# IP2366_DEMO_V1_41_1.net
KiCad netlist of a schematic drawn in Altium Designer
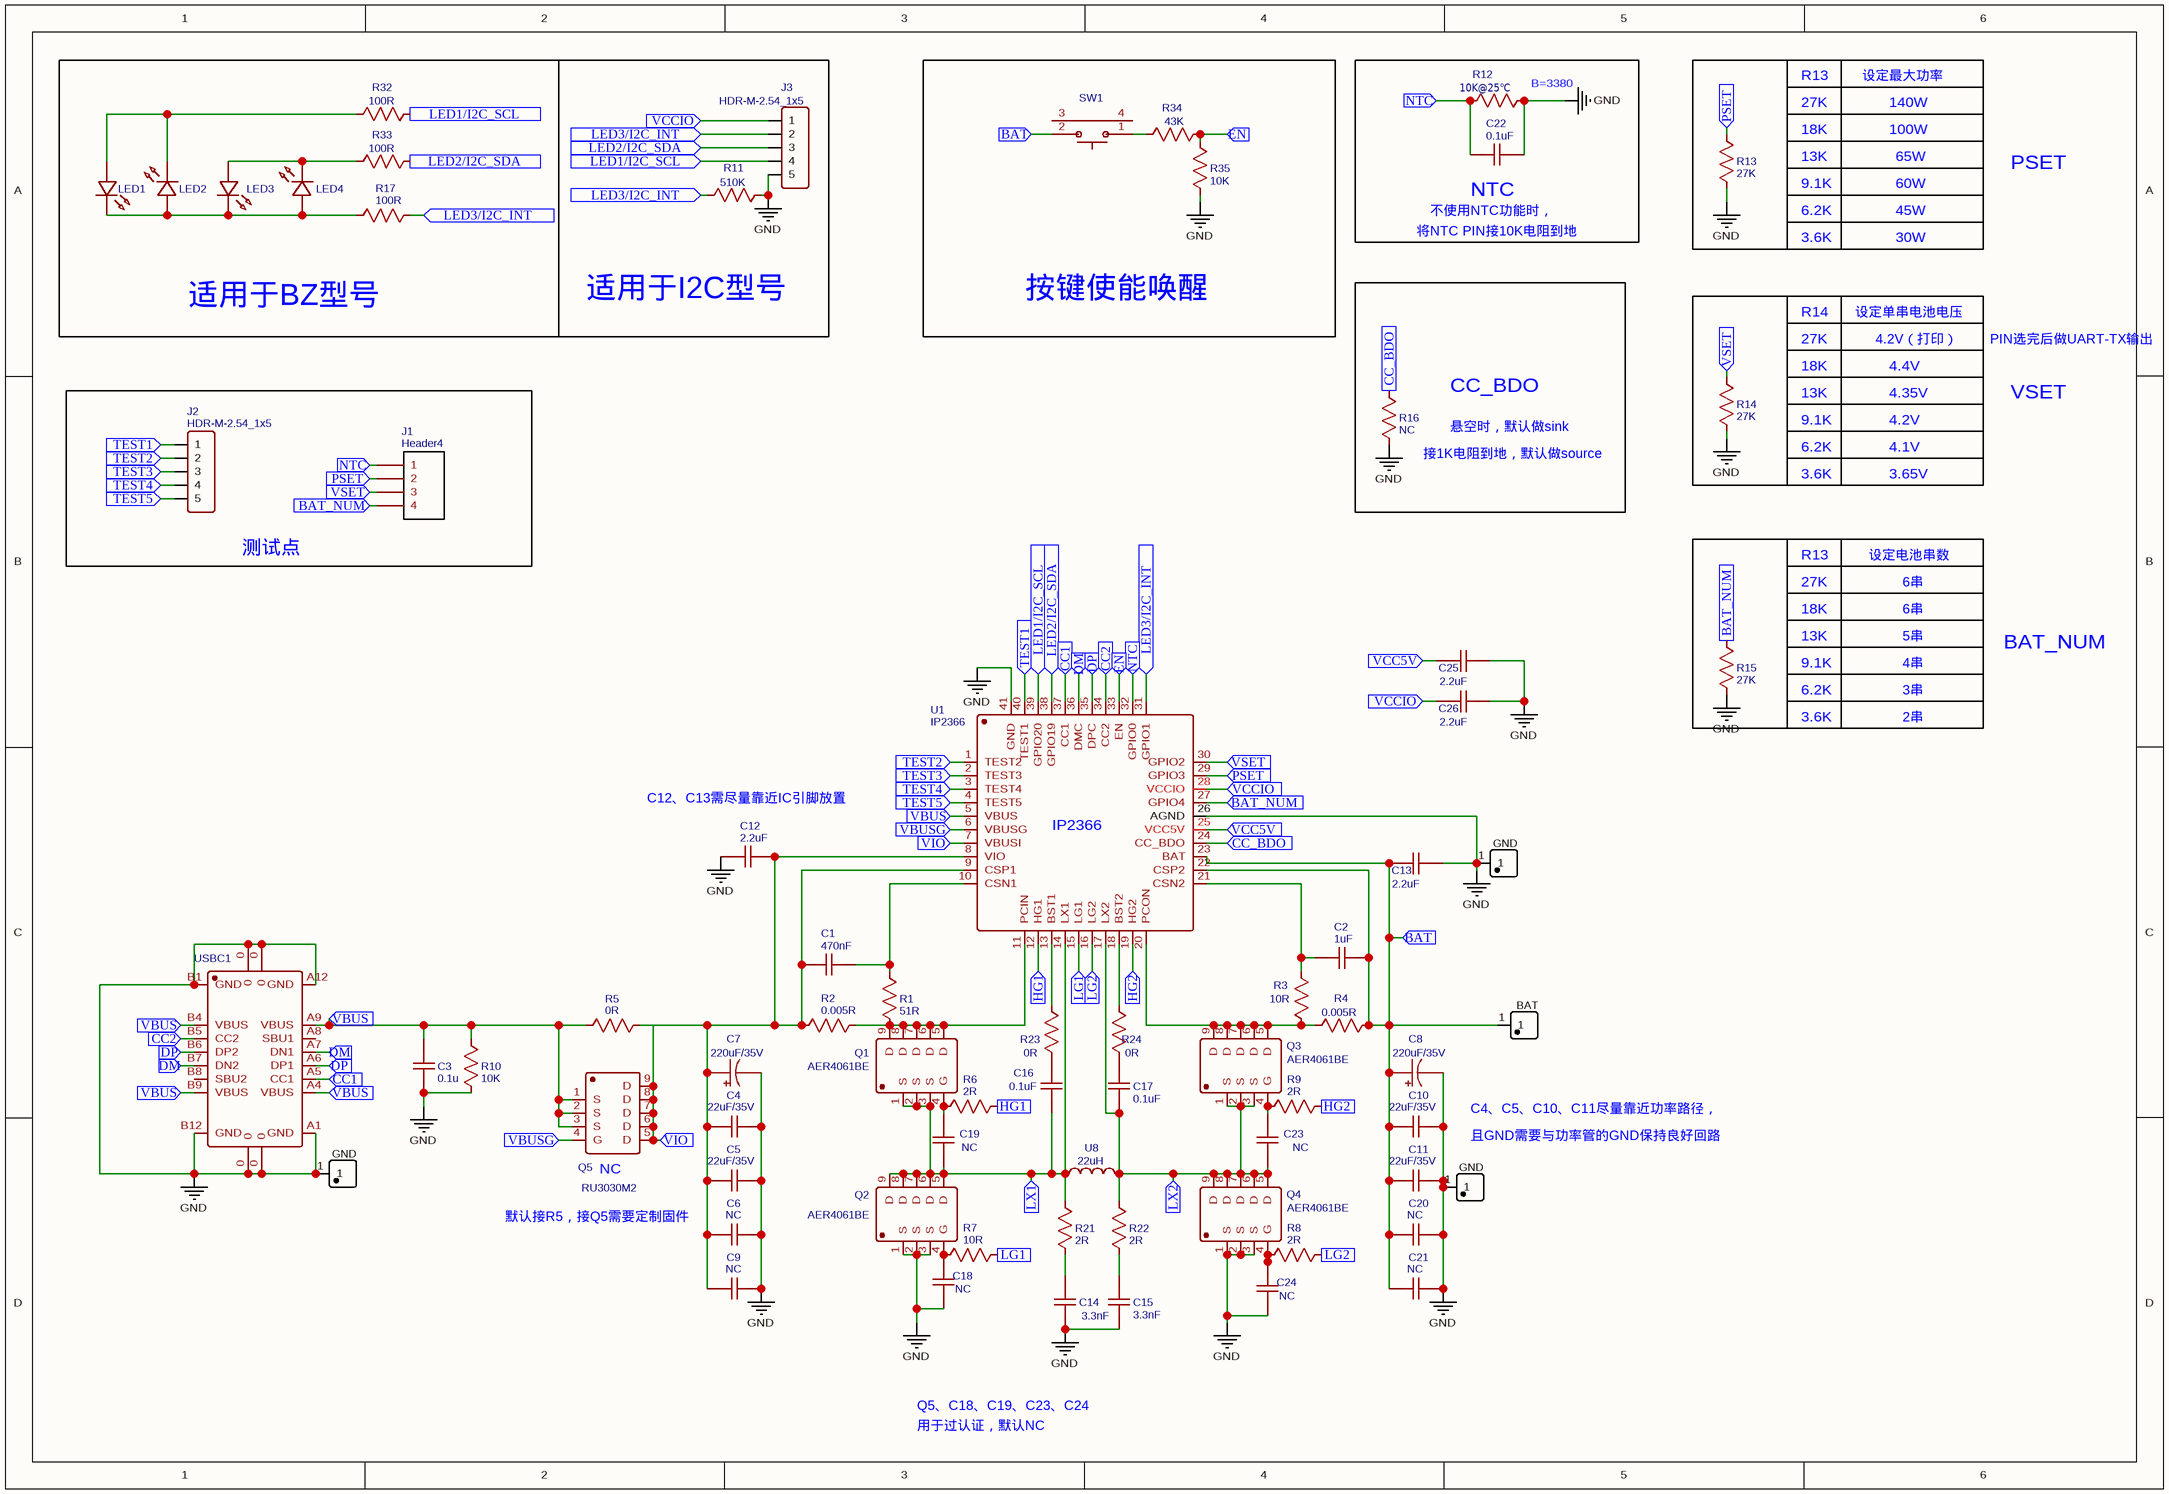
[diagram p0: IP2366_DEMO_V1.41(1).schdoc]

(export (version "E")
  (design (tool "Eeschema 10.0.6"))
  (components
    (comp (ref "C1")
      (value "470nF")
      (fields (field (name "CONTRIBUTOR") "LCEDA_Lib"))
      (libsource (lib "altium-import") (part "root_0_470nF_"))
    )
    (comp (ref "C2")
      (value "1uF")
      (fields (field (name "CONTRIBUTOR") "LCEDA_Lib"))
      (libsource (lib "altium-import") (part "root_0_1uF_"))
    )
    (comp (ref "C3")
      (value "0.1u")
      (fields (field (name "CONTRIBUTOR") "LCEDA_Lib"))
      (libsource (lib "altium-import") (part "root_1_0.1u_"))
    )
    (comp (ref "C4")
      (value "22uF/35V")
      (fields (field (name "CONTRIBUTOR") "LCEDA_Lib"))
      (libsource (lib "altium-import") (part "root_0_22uF/35V_"))
    )
    (comp (ref "C5")
      (value "22uF/35V")
      (fields (field (name "CONTRIBUTOR") "LCEDA_Lib"))
      (libsource (lib "altium-import") (part "root_0_22uF/35V_"))
    )
    (comp (ref "C6")
      (value "NC")
      (fields (field (name "CONTRIBUTOR") "LCEDA_Lib"))
      (libsource (lib "altium-import") (part "root_0_NC_"))
    )
    (comp (ref "C7")
      (value "220uF/35V")
      (fields
        (field (name "BOM_SUPPLIER PART") "C365767")
        (field (name "BOM_MANUFACTURER PART") "RC050M4R7LO5*11TH-2A1E")
        (field (name "CONTRIBUTOR") "s-dawn")
      )
      (libsource (lib "altium-import") (part "root_1_220uF/35V_"))
    )
    (comp (ref "C8")
      (value "220uF/35V")
      (fields
        (field (name "BOM_SUPPLIER PART") "C365767")
        (field (name "BOM_MANUFACTURER PART") "RC050M4R7LO5*11TH-2A1E")
        (field (name "CONTRIBUTOR") "s-dawn")
      )
      (libsource (lib "altium-import") (part "root_1_220uF/35V_"))
    )
    (comp (ref "C9")
      (value "NC")
      (fields (field (name "CONTRIBUTOR") "LCEDA_Lib"))
      (libsource (lib "altium-import") (part "root_0_NC_"))
    )
    (comp (ref "C10")
      (value "22uF/35V")
      (fields (field (name "CONTRIBUTOR") "LCEDA_Lib"))
      (libsource (lib "altium-import") (part "root_0_22uF/35V_"))
    )
    (comp (ref "C11")
      (value "22uF/35V")
      (fields (field (name "CONTRIBUTOR") "LCEDA_Lib"))
      (libsource (lib "altium-import") (part "root_0_22uF/35V_"))
    )
    (comp (ref "C12")
      (value "2.2uF")
      (fields (field (name "CONTRIBUTOR") "LCEDA_Lib"))
      (libsource (lib "altium-import") (part "root_0_2.2uF_"))
    )
    (comp (ref "C13")
      (value "2.2uF")
      (fields (field (name "CONTRIBUTOR") "LCEDA_Lib"))
      (libsource (lib "altium-import") (part "root_0_2.2uF_"))
    )
    (comp (ref "C14")
      (value "3.3nF")
      (fields (field (name "CONTRIBUTOR") "LCEDA_Lib"))
      (libsource (lib "altium-import") (part "root_3_3.3nF_"))
    )
    (comp (ref "C15")
      (value "3.3nF")
      (fields (field (name "CONTRIBUTOR") "LCEDA_Lib"))
      (libsource (lib "altium-import") (part "root_3_3.3nF_"))
    )
    (comp (ref "C16")
      (value "0.1uF")
      (fields (field (name "CONTRIBUTOR") "LCEDA_Lib"))
      (libsource (lib "altium-import") (part "root_3_0.1uF_"))
    )
    (comp (ref "C17")
      (value "0.1uF")
      (fields (field (name "CONTRIBUTOR") "LCEDA_Lib"))
      (libsource (lib "altium-import") (part "root_3_0.1uF_"))
    )
    (comp (ref "C18")
      (value "NC")
      (fields (field (name "CONTRIBUTOR") "LCEDA_Lib"))
      (libsource (lib "altium-import") (part "root_3_NC_"))
    )
    (comp (ref "C19")
      (value "NC")
      (fields (field (name "CONTRIBUTOR") "LCEDA_Lib"))
      (libsource (lib "altium-import") (part "root_3_NC_"))
    )
    (comp (ref "C20")
      (value "NC")
      (fields (field (name "CONTRIBUTOR") "LCEDA_Lib"))
      (libsource (lib "altium-import") (part "root_0_NC_"))
    )
    (comp (ref "C21")
      (value "NC")
      (fields (field (name "CONTRIBUTOR") "LCEDA_Lib"))
      (libsource (lib "altium-import") (part "root_0_NC_"))
    )
    (comp (ref "C22")
      (value "0.1uF")
      (fields (field (name "CONTRIBUTOR") "LCEDA_Lib"))
      (libsource (lib "altium-import") (part "root_0_0.1uF_"))
    )
    (comp (ref "C23")
      (value "NC")
      (fields (field (name "CONTRIBUTOR") "LCEDA_Lib"))
      (libsource (lib "altium-import") (part "root_3_NC_"))
    )
    (comp (ref "C24")
      (value "NC")
      (fields (field (name "CONTRIBUTOR") "LCEDA_Lib"))
      (libsource (lib "altium-import") (part "root_3_NC_"))
    )
    (comp (ref "C25")
      (value "2.2uF")
      (fields (field (name "CONTRIBUTOR") "LCEDA_Lib"))
      (libsource (lib "altium-import") (part "root_0_2.2uF_"))
    )
    (comp (ref "C26")
      (value "2.2uF")
      (fields (field (name "CONTRIBUTOR") "LCEDA_Lib"))
      (libsource (lib "altium-import") (part "root_0_2.2uF_"))
    )
    (comp (ref "J1")
      (value "Header4")
      (fields (field (name "CONTRIBUTOR") "hrqmmm1"))
      (libsource (lib "altium-import") (part "root_2_Header4_"))
    )
    (comp (ref "J2")
      (value "HDR-M-2.54_1x5")
      (fields (field (name "BOM_SUPPLIER PART") "C358687") (field (name "CONTRIBUTOR") "LCEDA_Lib"))
      (libsource (lib "altium-import") (part "root_0_HDR-M-2.54_1x5_"))
    )
    (comp (ref "J3")
      (value "HDR-M-2.54_1x5")
      (fields (field (name "BOM_SUPPLIER PART") "C358687") (field (name "CONTRIBUTOR") "LCEDA_Lib"))
      (libsource (lib "altium-import") (part "root_0_HDR-M-2.54_1x5_"))
    )
    (comp (ref "LED1")
      (value "LED-0603_B")
      (fields
        (field (name "BOM_MANUFACTURER PART") "19-217/BHC-ZL1M2RY/3T")
        (field (name "BOM_SUPPLIER PART") "C72041")
        (field (name "CONTRIBUTOR") "LCEDA_01")
      )
      (libsource (lib "altium-import") (part "root_3_LED-0603_B_"))
    )
    (comp (ref "LED2")
      (value "LED-0603_B")
      (fields
        (field (name "BOM_MANUFACTURER PART") "19-217/BHC-ZL1M2RY/3T")
        (field (name "BOM_SUPPLIER PART") "C72041")
        (field (name "CONTRIBUTOR") "LCEDA_01")
      )
      (libsource (lib "altium-import") (part "root_1_LED-0603_B_"))
    )
    (comp (ref "LED3")
      (value "LED-0603_B")
      (fields
        (field (name "BOM_MANUFACTURER PART") "19-217/BHC-ZL1M2RY/3T")
        (field (name "BOM_SUPPLIER PART") "C72041")
        (field (name "CONTRIBUTOR") "LCEDA_01")
      )
      (libsource (lib "altium-import") (part "root_3_LED-0603_B_"))
    )
    (comp (ref "LED4")
      (value "LED-0603_B")
      (fields
        (field (name "BOM_MANUFACTURER PART") "19-217/BHC-ZL1M2RY/3T")
        (field (name "BOM_SUPPLIER PART") "C72041")
        (field (name "CONTRIBUTOR") "LCEDA_01")
      )
      (libsource (lib "altium-import") (part "root_1_LED-0603_B_"))
    )
    (comp (ref "Q1")
      (value "AER4061BE")
      (fields
        (field (name "BOM_MANUFACTURER PART") "RU3090M")
        (field (name "BOM_SUPPLIER PART") "C160654")
        (field (name "CONTRIBUTOR") "LCSC")
      )
      (libsource (lib "altium-import") (part "root_1_AER4061BE_"))
    )
    (comp (ref "Q2")
      (value "AER4061BE")
      (fields
        (field (name "BOM_MANUFACTURER PART") "RU3090M")
        (field (name "BOM_SUPPLIER PART") "C160654")
        (field (name "CONTRIBUTOR") "LCSC")
      )
      (libsource (lib "altium-import") (part "root_1_AER4061BE_"))
    )
    (comp (ref "Q3")
      (value "AER4061BE")
      (fields
        (field (name "BOM_MANUFACTURER PART") "RU3090M")
        (field (name "BOM_SUPPLIER PART") "C160654")
        (field (name "CONTRIBUTOR") "LCSC")
      )
      (libsource (lib "altium-import") (part "root_1_AER4061BE_"))
    )
    (comp (ref "Q4")
      (value "AER4061BE")
      (fields
        (field (name "BOM_MANUFACTURER PART") "RU3090M")
        (field (name "BOM_SUPPLIER PART") "C160654")
        (field (name "CONTRIBUTOR") "LCSC")
      )
      (libsource (lib "altium-import") (part "root_1_AER4061BE_"))
    )
    (comp (ref "Q5")
      (value "RU3030M2")
      (fields (field (name "BOM_SUPPLIER PART") "C180957") (field (name "CONTRIBUTOR") "LCSC"))
      (libsource (lib "altium-import") (part "root_0_RU3030M2_"))
    )
    (comp (ref "R1")
      (value "51R")
      (fields (field (name "CONTRIBUTOR") "LCEDA_Lib"))
      (libsource (lib "altium-import") (part "root_1_51R_"))
    )
    (comp (ref "R2")
      (value "0.005R")
      (fields (field (name "CONTRIBUTOR") "LCEDA_Lib"))
      (libsource (lib "altium-import") (part "root_0_0.005R_"))
    )
    (comp (ref "R3")
      (value "10R")
      (fields (field (name "CONTRIBUTOR") "LCEDA_Lib"))
      (libsource (lib "altium-import") (part "root_1_10R_"))
    )
    (comp (ref "R4")
      (value "0.005R")
      (fields (field (name "CONTRIBUTOR") "LCEDA_Lib"))
      (libsource (lib "altium-import") (part "root_0_0.005R_"))
    )
    (comp (ref "R5")
      (value "0R")
      (fields (field (name "CONTRIBUTOR") "LCEDA_Lib"))
      (libsource (lib "altium-import") (part "root_0_0R_"))
    )
    (comp (ref "R6")
      (value "2R")
      (fields (field (name "CONTRIBUTOR") "LCEDA_Lib"))
      (libsource (lib "altium-import") (part "root_0_2R_"))
    )
    (comp (ref "R7")
      (value "10R")
      (fields (field (name "CONTRIBUTOR") "LCEDA_Lib"))
      (libsource (lib "altium-import") (part "root_0_10R_"))
    )
    (comp (ref "R8")
      (value "2R")
      (fields (field (name "CONTRIBUTOR") "LCEDA_Lib"))
      (libsource (lib "altium-import") (part "root_0_2R_"))
    )
    (comp (ref "R9")
      (value "2R")
      (fields (field (name "CONTRIBUTOR") "LCEDA_Lib"))
      (libsource (lib "altium-import") (part "root_0_2R_"))
    )
    (comp (ref "R10")
      (value "10K")
      (fields (field (name "CONTRIBUTOR") "LCEDA_Lib"))
      (libsource (lib "altium-import") (part "root_3_10K_"))
    )
    (comp (ref "R11")
      (value "510K")
      (fields (field (name "CONTRIBUTOR") "LCEDA_Lib"))
      (libsource (lib "altium-import") (part "root_0_510K_"))
    )
    (comp (ref "R12")
      (value "10K@25℃")
      (fields (field (name "CONTRIBUTOR") "LCEDA_Lib"))
      (libsource (lib "altium-import") (part "root_2_10K@25℃_"))
    )
    (comp (ref "R13")
      (value "27K")
      (fields (field (name "CONTRIBUTOR") "LCEDA_Lib"))
      (libsource (lib "altium-import") (part "root_1_27K_"))
    )
    (comp (ref "R14")
      (value "27K")
      (fields (field (name "CONTRIBUTOR") "LCEDA_Lib"))
      (libsource (lib "altium-import") (part "root_1_27K_"))
    )
    (comp (ref "R15")
      (value "27K")
      (fields (field (name "CONTRIBUTOR") "LCEDA_Lib"))
      (libsource (lib "altium-import") (part "root_1_27K_"))
    )
    (comp (ref "R16")
      (value "NC")
      (fields (field (name "CONTRIBUTOR") "LCEDA_Lib"))
      (libsource (lib "altium-import") (part "root_1_NC_"))
    )
    (comp (ref "R17")
      (value "100R")
      (fields (field (name "CONTRIBUTOR") "LCEDA_Lib"))
      (libsource (lib "altium-import") (part "root_0_100R_"))
    )
    (comp (ref "R21")
      (value "2R")
      (fields (field (name "CONTRIBUTOR") "LCEDA_Lib"))
      (libsource (lib "altium-import") (part "root_1_2R_"))
    )
    (comp (ref "R22")
      (value "2R")
      (fields (field (name "CONTRIBUTOR") "LCEDA_Lib"))
      (libsource (lib "altium-import") (part "root_1_2R_"))
    )
    (comp (ref "R23")
      (value "0R")
      (fields (field (name "CONTRIBUTOR") "LCEDA_Lib"))
      (libsource (lib "altium-import") (part "root_3_0R_"))
    )
    (comp (ref "R24")
      (value "0R")
      (fields (field (name "CONTRIBUTOR") "LCEDA_Lib"))
      (libsource (lib "altium-import") (part "root_1_0R_"))
    )
    (comp (ref "R32")
      (value "100R")
      (fields (field (name "CONTRIBUTOR") "LCEDA_Lib"))
      (libsource (lib "altium-import") (part "root_2_100R_"))
    )
    (comp (ref "R33")
      (value "100R")
      (fields (field (name "CONTRIBUTOR") "LCEDA_Lib"))
      (libsource (lib "altium-import") (part "root_2_100R_"))
    )
    (comp (ref "R34")
      (value "43K")
      (fields (field (name "CONTRIBUTOR") "LCEDA_Lib"))
      (libsource (lib "altium-import") (part "root_2_43K_"))
    )
    (comp (ref "R35")
      (value "10K")
      (fields (field (name "CONTRIBUTOR") "LCEDA_Lib"))
      (libsource (lib "altium-import") (part "root_3_10K_"))
    )
    (comp (ref "SW1")
      (value "1TS002G-1900-3500-CT")
      (fields (field (name "BOM_SUPPLIER PART") "C319376") (field (name "CONTRIBUTOR") "LCSC"))
      (libsource (lib "altium-import") (part "root_2_1TS002G-1900-3500-CT_"))
    )
    (comp (ref "U1")
      (value "IP2366")
      (fields (field (name "CONTRIBUTOR") "cong24"))
      (libsource (lib "altium-import") (part "root_0_IP2366_"))
    )
    (comp (ref "U3")
      (value "GND")
      (fields
        (field (name "BOM_SUPPLIER PART") "C9900007423")
        (field (name "BOM_MANUFACTURER PART") "TP-红色测试点")
        (field (name "CONTRIBUTOR") "lcsc")
      )
      (libsource (lib "altium-import") (part "root_2_GND_"))
    )
    (comp (ref "U4")
      (value "BAT")
      (fields
        (field (name "BOM_SUPPLIER PART") "C9900007423")
        (field (name "BOM_MANUFACTURER PART") "TP-红色测试点")
        (field (name "CONTRIBUTOR") "lcsc")
      )
      (libsource (lib "altium-import") (part "root_2_BAT_"))
    )
    (comp (ref "U5")
      (value "GND")
      (fields
        (field (name "BOM_SUPPLIER PART") "C9900007423")
        (field (name "BOM_MANUFACTURER PART") "TP-红色测试点")
        (field (name "CONTRIBUTOR") "lcsc")
      )
      (libsource (lib "altium-import") (part "root_2_GND_"))
    )
    (comp (ref "U8")
      (value "22uH")
      (fields
        (field (name "BOM_SUPPLIER PART") "C3011538")
        (field (name "BOM_MANUFACTURER PART") "PDMTAT068125-100MLU")
        (field (name "CONTRIBUTOR") "lcsc")
      )
      (libsource (lib "altium-import") (part "root_0_22uH_"))
    )
    (comp (ref "U9")
      (value "GND")
      (fields
        (field (name "BOM_SUPPLIER PART") "C9900007423")
        (field (name "BOM_MANUFACTURER PART") "TP-红色测试点")
        (field (name "CONTRIBUTOR") "lcsc")
      )
      (libsource (lib "altium-import") (part "root_2_GND_"))
    )
    (comp (ref "USBC1")
      (value "TYPE-C-31-M-12")
      (fields (field (name "BOM_SUPPLIER PART") "C165948") (field (name "CONTRIBUTOR") "LCSC"))
      (libsource (lib "altium-import") (part "root_0_TYPE-C-31-M-12_"))
    )
  )
  (nets
    (net (code "1") (name "/BAT") (class "Default")
      (node (ref "C10") (pin "1") (pinfunction "1_1") (pintype "passive"))
      (node (ref "C11") (pin "1") (pinfunction "1_1") (pintype "passive"))
      (node (ref "C13") (pin "1") (pinfunction "1_1") (pintype "passive"))
      (node (ref "C2") (pin "2") (pinfunction "2_2") (pintype "passive"))
      (node (ref "C20") (pin "1") (pinfunction "1_1") (pintype "passive"))
      (node (ref "C21") (pin "1") (pinfunction "1_1") (pintype "passive"))
      (node (ref "C8") (pin "1") (pinfunction "1_1") (pintype "passive"))
      (node (ref "R4") (pin "2") (pinfunction "2_2") (pintype "passive"))
      (node (ref "SW1") (pin "2") (pinfunction "2_2") (pintype "passive"))
      (node (ref "U1") (pin "22") (pinfunction "CSP2_22") (pintype "passive"))
      (node (ref "U1") (pin "23") (pinfunction "BAT_23") (pintype "passive"))
      (node (ref "U4") (pin "1") (pinfunction "1_1") (pintype "passive"))
    )
    (net (code "2") (name "/BAT_NUM") (class "Default")
      (node (ref "J1") (pin "4") (pinfunction "4_4") (pintype "passive"))
      (node (ref "R15") (pin "2") (pinfunction "2_2") (pintype "passive"))
      (node (ref "U1") (pin "27") (pinfunction "GPIO4_27") (pintype "passive"))
    )
    (net (code "3") (name "/CC1") (class "Default")
      (node (ref "U1") (pin "37") (pinfunction "CC1_37") (pintype "passive"))
      (node (ref "USBC1") (pin "A5") (pinfunction "CC1_A5") (pintype "passive"))
    )
    (net (code "4") (name "/CC2") (class "Default")
      (node (ref "U1") (pin "34") (pinfunction "CC2_34") (pintype "passive"))
      (node (ref "USBC1") (pin "B5") (pinfunction "CC2_B5") (pintype "passive"))
    )
    (net (code "5") (name "/CC_BDO") (class "Default")
      (node (ref "R16") (pin "2") (pinfunction "2_2") (pintype "passive"))
      (node (ref "U1") (pin "24") (pinfunction "CC_BDO_24") (pintype "passive"))
    )
    (net (code "6") (name "/DM") (class "Default")
      (node (ref "U1") (pin "36") (pinfunction "DMC_36") (pintype "passive"))
      (node (ref "USBC1") (pin "A7") (pinfunction "DN1_A7") (pintype "passive"))
      (node (ref "USBC1") (pin "B7") (pinfunction "DN2_B7") (pintype "passive"))
    )
    (net (code "7") (name "/DP") (class "Default")
      (node (ref "U1") (pin "35") (pinfunction "DPC_35") (pintype "passive"))
      (node (ref "USBC1") (pin "A6") (pinfunction "DP1_A6") (pintype "passive"))
      (node (ref "USBC1") (pin "B6") (pinfunction "DP2_B6") (pintype "passive"))
    )
    (net (code "8") (name "/EN") (class "Default")
      (node (ref "R34") (pin "1") (pinfunction "1_1") (pintype "passive"))
      (node (ref "R35") (pin "1") (pinfunction "1_1") (pintype "passive"))
      (node (ref "U1") (pin "33") (pinfunction "EN_33") (pintype "passive"))
    )
    (net (code "9") (name "/HG1") (class "Default")
      (node (ref "R6") (pin "2") (pinfunction "2_2") (pintype "passive"))
      (node (ref "U1") (pin "12") (pinfunction "HG1_12") (pintype "passive"))
    )
    (net (code "10") (name "/HG2") (class "Default")
      (node (ref "R9") (pin "2") (pinfunction "2_2") (pintype "passive"))
      (node (ref "U1") (pin "19") (pinfunction "HG2_19") (pintype "passive"))
    )
    (net (code "11") (name "/LED1{slash}I2C_SCL") (class "Default")
      (node (ref "J3") (pin "4") (pinfunction "4_4") (pintype "passive"))
      (node (ref "R32") (pin "1") (pinfunction "1_1") (pintype "passive"))
      (node (ref "U1") (pin "39") (pinfunction "GPIO20_39") (pintype "passive"))
    )
    (net (code "12") (name "/LED2{slash}I2C_SDA") (class "Default")
      (node (ref "J3") (pin "3") (pinfunction "3_3") (pintype "passive"))
      (node (ref "R33") (pin "1") (pinfunction "1_1") (pintype "passive"))
      (node (ref "U1") (pin "38") (pinfunction "GPIO19_38") (pintype "passive"))
    )
    (net (code "13") (name "/LED3{slash}I2C_INT") (class "Default")
      (node (ref "J3") (pin "2") (pinfunction "2_2") (pintype "passive"))
      (node (ref "R11") (pin "1") (pinfunction "1_1") (pintype "passive"))
      (node (ref "R17") (pin "2") (pinfunction "2_2") (pintype "passive"))
      (node (ref "U1") (pin "31") (pinfunction "GPIO1_31") (pintype "passive"))
    )
    (net (code "14") (name "/LG1") (class "Default")
      (node (ref "R7") (pin "2") (pinfunction "2_2") (pintype "passive"))
      (node (ref "U1") (pin "15") (pinfunction "LG1_15") (pintype "passive"))
    )
    (net (code "15") (name "/LG2") (class "Default")
      (node (ref "R8") (pin "2") (pinfunction "2_2") (pintype "passive"))
      (node (ref "U1") (pin "16") (pinfunction "LG2_16") (pintype "passive"))
    )
    (net (code "16") (name "/LX1") (class "Default")
      (node (ref "C16") (pin "2") (pinfunction "2_2") (pintype "passive"))
      (node (ref "C19") (pin "2") (pinfunction "2_2") (pintype "passive"))
      (node (ref "Q1") (pin "1") (pinfunction "S_1") (pintype "passive"))
      (node (ref "Q1") (pin "2") (pinfunction "S_2") (pintype "passive"))
      (node (ref "Q1") (pin "3") (pinfunction "S_3") (pintype "passive"))
      (node (ref "Q2") (pin "5") (pinfunction "D_5") (pintype "passive"))
      (node (ref "Q2") (pin "6") (pinfunction "D_6") (pintype "passive"))
      (node (ref "Q2") (pin "7") (pinfunction "D_7") (pintype "passive"))
      (node (ref "Q2") (pin "8") (pinfunction "D_8") (pintype "passive"))
      (node (ref "Q2") (pin "9") (pinfunction "D_9") (pintype "passive"))
      (node (ref "R21") (pin "2") (pinfunction "2_2") (pintype "passive"))
      (node (ref "U1") (pin "14") (pinfunction "LX1_14") (pintype "passive"))
      (node (ref "U8") (pin "1") (pinfunction "1_1") (pintype "passive"))
    )
    (net (code "17") (name "/LX2") (class "Default")
      (node (ref "C17") (pin "2") (pinfunction "2_2") (pintype "passive"))
      (node (ref "C23") (pin "2") (pinfunction "2_2") (pintype "passive"))
      (node (ref "Q3") (pin "1") (pinfunction "S_1") (pintype "passive"))
      (node (ref "Q3") (pin "2") (pinfunction "S_2") (pintype "passive"))
      (node (ref "Q3") (pin "3") (pinfunction "S_3") (pintype "passive"))
      (node (ref "Q4") (pin "5") (pinfunction "D_5") (pintype "passive"))
      (node (ref "Q4") (pin "6") (pinfunction "D_6") (pintype "passive"))
      (node (ref "Q4") (pin "7") (pinfunction "D_7") (pintype "passive"))
      (node (ref "Q4") (pin "8") (pinfunction "D_8") (pintype "passive"))
      (node (ref "Q4") (pin "9") (pinfunction "D_9") (pintype "passive"))
      (node (ref "R22") (pin "2") (pinfunction "2_2") (pintype "passive"))
      (node (ref "U1") (pin "17") (pinfunction "LX2_17") (pintype "passive"))
      (node (ref "U8") (pin "2") (pinfunction "2_2") (pintype "passive"))
    )
    (net (code "18") (name "/NTC") (class "Default")
      (node (ref "C22") (pin "1") (pinfunction "1_1") (pintype "passive"))
      (node (ref "J1") (pin "1") (pinfunction "1_1") (pintype "passive"))
      (node (ref "R12") (pin "2") (pinfunction "2_2") (pintype "passive"))
      (node (ref "U1") (pin "32") (pinfunction "GPIO0_32") (pintype "passive"))
    )
    (net (code "19") (name "/PSET") (class "Default")
      (node (ref "J1") (pin "2") (pinfunction "2_2") (pintype "passive"))
      (node (ref "R13") (pin "2") (pinfunction "2_2") (pintype "passive"))
      (node (ref "U1") (pin "29") (pinfunction "GPIO3_29") (pintype "passive"))
    )
    (net (code "20") (name "/TEST1") (class "Default")
      (node (ref "J2") (pin "1") (pinfunction "1_1") (pintype "passive"))
      (node (ref "U1") (pin "40") (pinfunction "TEST1_40") (pintype "passive"))
    )
    (net (code "21") (name "/TEST2") (class "Default")
      (node (ref "J2") (pin "2") (pinfunction "2_2") (pintype "passive"))
      (node (ref "U1") (pin "1") (pinfunction "TEST2_1") (pintype "passive"))
    )
    (net (code "22") (name "/TEST3") (class "Default")
      (node (ref "J2") (pin "3") (pinfunction "3_3") (pintype "passive"))
      (node (ref "U1") (pin "2") (pinfunction "TEST3_2") (pintype "passive"))
    )
    (net (code "23") (name "/TEST4") (class "Default")
      (node (ref "J2") (pin "4") (pinfunction "4_4") (pintype "passive"))
      (node (ref "U1") (pin "3") (pinfunction "TEST4_3") (pintype "passive"))
    )
    (net (code "24") (name "/TEST5") (class "Default")
      (node (ref "J2") (pin "5") (pinfunction "5_5") (pintype "passive"))
      (node (ref "U1") (pin "4") (pinfunction "TEST5_4") (pintype "passive"))
    )
    (net (code "25") (name "/VBUS") (class "Default")
      (node (ref "C3") (pin "2") (pinfunction "2_2") (pintype "passive"))
      (node (ref "Q5") (pin "1") (pinfunction "S_1") (pintype "passive"))
      (node (ref "Q5") (pin "2") (pinfunction "S_2") (pintype "passive"))
      (node (ref "Q5") (pin "3") (pinfunction "S_3") (pintype "passive"))
      (node (ref "R10") (pin "1") (pinfunction "1_1") (pintype "passive"))
      (node (ref "R5") (pin "1") (pinfunction "1_1") (pintype "passive"))
      (node (ref "U1") (pin "5") (pinfunction "VBUS_5") (pintype "passive"))
      (node (ref "USBC1") (pin "A4") (pinfunction "VBUS_A4") (pintype "passive"))
      (node (ref "USBC1") (pin "A9") (pinfunction "VBUS_A9") (pintype "passive"))
      (node (ref "USBC1") (pin "B4") (pinfunction "VBUS_B4") (pintype "passive"))
      (node (ref "USBC1") (pin "B9") (pinfunction "VBUS_B9") (pintype "passive"))
    )
    (net (code "26") (name "/VBUSG") (class "Default")
      (node (ref "Q5") (pin "4") (pinfunction "G_4") (pintype "passive"))
      (node (ref "U1") (pin "6") (pinfunction "VBUSG_6") (pintype "passive"))
    )
    (net (code "27") (name "/VCC5V") (class "Default")
      (node (ref "C25") (pin "1") (pinfunction "1_1") (pintype "passive"))
      (node (ref "U1") (pin "25") (pinfunction "VCC5V_25") (pintype "passive"))
    )
    (net (code "28") (name "/VCCIO") (class "Default")
      (node (ref "C26") (pin "1") (pinfunction "1_1") (pintype "passive"))
      (node (ref "J3") (pin "1") (pinfunction "1_1") (pintype "passive"))
      (node (ref "U1") (pin "28") (pinfunction "VCCIO_28") (pintype "passive"))
    )
    (net (code "29") (name "/VIO") (class "Default")
      (node (ref "C1") (pin "1") (pinfunction "1_1") (pintype "passive"))
      (node (ref "C12") (pin "2") (pinfunction "2_2") (pintype "passive"))
      (node (ref "C4") (pin "1") (pinfunction "1_1") (pintype "passive"))
      (node (ref "C5") (pin "1") (pinfunction "1_1") (pintype "passive"))
      (node (ref "C6") (pin "1") (pinfunction "1_1") (pintype "passive"))
      (node (ref "C7") (pin "1") (pinfunction "1_1") (pintype "passive"))
      (node (ref "C9") (pin "1") (pinfunction "1_1") (pintype "passive"))
      (node (ref "Q5") (pin "5") (pinfunction "D_5") (pintype "passive"))
      (node (ref "Q5") (pin "6") (pinfunction "D_6") (pintype "passive"))
      (node (ref "Q5") (pin "7") (pinfunction "D_7") (pintype "passive"))
      (node (ref "Q5") (pin "8") (pinfunction "D_8") (pintype "passive"))
      (node (ref "Q5") (pin "9") (pinfunction "D_9") (pintype "passive"))
      (node (ref "R2") (pin "1") (pinfunction "1_1") (pintype "passive"))
      (node (ref "R5") (pin "2") (pinfunction "2_2") (pintype "passive"))
      (node (ref "U1") (pin "7") (pinfunction "VBUSI_7") (pintype "passive"))
      (node (ref "U1") (pin "8") (pinfunction "VIO_8") (pintype "passive"))
      (node (ref "U1") (pin "9") (pinfunction "CSP1_9") (pintype "passive"))
    )
    (net (code "30") (name "/VSET") (class "Default")
      (node (ref "J1") (pin "3") (pinfunction "3_3") (pintype "passive"))
      (node (ref "R14") (pin "2") (pinfunction "2_2") (pintype "passive"))
      (node (ref "U1") (pin "30") (pinfunction "GPIO2_30") (pintype "passive"))
    )
    (net (code "31") (name "GND") (class "Default")
      (node (ref "C10") (pin "2") (pinfunction "2_2") (pintype "passive"))
      (node (ref "C11") (pin "2") (pinfunction "2_2") (pintype "passive"))
      (node (ref "C12") (pin "1") (pinfunction "1_1") (pintype "passive"))
      (node (ref "C13") (pin "2") (pinfunction "2_2") (pintype "passive"))
      (node (ref "C14") (pin "2") (pinfunction "2_2") (pintype "passive"))
      (node (ref "C15") (pin "2") (pinfunction "2_2") (pintype "passive"))
      (node (ref "C18") (pin "2") (pinfunction "2_2") (pintype "passive"))
      (node (ref "C20") (pin "2") (pinfunction "2_2") (pintype "passive"))
      (node (ref "C21") (pin "2") (pinfunction "2_2") (pintype "passive"))
      (node (ref "C22") (pin "2") (pinfunction "2_2") (pintype "passive"))
      (node (ref "C24") (pin "2") (pinfunction "2_2") (pintype "passive"))
      (node (ref "C25") (pin "2") (pinfunction "2_2") (pintype "passive"))
      (node (ref "C26") (pin "2") (pinfunction "2_2") (pintype "passive"))
      (node (ref "C3") (pin "1") (pinfunction "1_1") (pintype "passive"))
      (node (ref "C4") (pin "2") (pinfunction "2_2") (pintype "passive"))
      (node (ref "C5") (pin "2") (pinfunction "2_2") (pintype "passive"))
      (node (ref "C6") (pin "2") (pinfunction "2_2") (pintype "passive"))
      (node (ref "C7") (pin "2") (pinfunction "2_2") (pintype "passive"))
      (node (ref "C8") (pin "2") (pinfunction "2_2") (pintype "passive"))
      (node (ref "C9") (pin "2") (pinfunction "2_2") (pintype "passive"))
      (node (ref "J3") (pin "5") (pinfunction "5_5") (pintype "passive"))
      (node (ref "Q2") (pin "1") (pinfunction "S_1") (pintype "passive"))
      (node (ref "Q2") (pin "2") (pinfunction "S_2") (pintype "passive"))
      (node (ref "Q2") (pin "3") (pinfunction "S_3") (pintype "passive"))
      (node (ref "Q4") (pin "1") (pinfunction "S_1") (pintype "passive"))
      (node (ref "Q4") (pin "2") (pinfunction "S_2") (pintype "passive"))
      (node (ref "Q4") (pin "3") (pinfunction "S_3") (pintype "passive"))
      (node (ref "R10") (pin "2") (pinfunction "2_2") (pintype "passive"))
      (node (ref "R11") (pin "2") (pinfunction "2_2") (pintype "passive"))
      (node (ref "R12") (pin "1") (pinfunction "1_1") (pintype "passive"))
      (node (ref "R13") (pin "1") (pinfunction "1_1") (pintype "passive"))
      (node (ref "R14") (pin "1") (pinfunction "1_1") (pintype "passive"))
      (node (ref "R15") (pin "1") (pinfunction "1_1") (pintype "passive"))
      (node (ref "R16") (pin "1") (pinfunction "1_1") (pintype "passive"))
      (node (ref "R35") (pin "2") (pinfunction "2_2") (pintype "passive"))
      (node (ref "U1") (pin "26") (pinfunction "AGND_26") (pintype "passive"))
      (node (ref "U1") (pin "41") (pinfunction "GND_41") (pintype "passive"))
      (node (ref "U3") (pin "1") (pinfunction "1_1") (pintype "passive"))
      (node (ref "U5") (pin "1") (pinfunction "1_1") (pintype "passive"))
      (node (ref "U9") (pin "1") (pinfunction "1_1") (pintype "passive"))
      (node (ref "USBC1") (pin "0") (pinfunction "0_0") (pintype "passive"))
      (node (ref "USBC1") (pin "A1") (pinfunction "GND_A1") (pintype "passive"))
      (node (ref "USBC1") (pin "A12") (pinfunction "GND_A12") (pintype "passive"))
      (node (ref "USBC1") (pin "B1") (pinfunction "GND_B1") (pintype "passive"))
      (node (ref "USBC1") (pin "B12") (pinfunction "GND_B12") (pintype "passive"))
    )
    (net (code "32") (name "Net-(C14-Pad1)") (class "Default")
      (node (ref "C14") (pin "1") (pinfunction "1_1") (pintype "passive"))
      (node (ref "R21") (pin "1") (pinfunction "1_1") (pintype "passive"))
    )
    (net (code "33") (name "Net-(C15-Pad1)") (class "Default")
      (node (ref "C15") (pin "1") (pinfunction "1_1") (pintype "passive"))
      (node (ref "R22") (pin "1") (pinfunction "1_1") (pintype "passive"))
    )
    (net (code "34") (name "Net-(C16-Pad1)") (class "Default")
      (node (ref "C16") (pin "1") (pinfunction "1_1") (pintype "passive"))
      (node (ref "R23") (pin "2") (pinfunction "2_2") (pintype "passive"))
    )
    (net (code "35") (name "Net-(C17-Pad1)") (class "Default")
      (node (ref "C17") (pin "1") (pinfunction "1_1") (pintype "passive"))
      (node (ref "R24") (pin "1") (pinfunction "1_1") (pintype "passive"))
    )
    (net (code "36") (name "Net-(LED1-Pad1)") (class "Default")
      (node (ref "LED1") (pin "1") (pinfunction "1_1") (pintype "passive"))
      (node (ref "LED2") (pin "2") (pinfunction "2_2") (pintype "passive"))
      (node (ref "R32") (pin "2") (pinfunction "2_2") (pintype "passive"))
    )
    (net (code "37") (name "Net-(LED1-Pad2)") (class "Default")
      (node (ref "LED1") (pin "2") (pinfunction "2_2") (pintype "passive"))
      (node (ref "LED2") (pin "1") (pinfunction "1_1") (pintype "passive"))
      (node (ref "LED3") (pin "2") (pinfunction "2_2") (pintype "passive"))
      (node (ref "LED4") (pin "1") (pinfunction "1_1") (pintype "passive"))
      (node (ref "R17") (pin "1") (pinfunction "1_1") (pintype "passive"))
    )
    (net (code "38") (name "Net-(LED3-Pad1)") (class "Default")
      (node (ref "LED3") (pin "1") (pinfunction "1_1") (pintype "passive"))
      (node (ref "LED4") (pin "2") (pinfunction "2_2") (pintype "passive"))
      (node (ref "R33") (pin "2") (pinfunction "2_2") (pintype "passive"))
    )
    (net (code "39") (name "Net-(Q1-G)") (class "Default")
      (node (ref "C19") (pin "1") (pinfunction "1_1") (pintype "passive"))
      (node (ref "Q1") (pin "4") (pinfunction "G_4") (pintype "passive"))
      (node (ref "R6") (pin "1") (pinfunction "1_1") (pintype "passive"))
    )
    (net (code "40") (name "Net-(Q2-G)") (class "Default")
      (node (ref "C18") (pin "1") (pinfunction "1_1") (pintype "passive"))
      (node (ref "Q2") (pin "4") (pinfunction "G_4") (pintype "passive"))
      (node (ref "R7") (pin "1") (pinfunction "1_1") (pintype "passive"))
    )
    (net (code "41") (name "Net-(Q3-G)") (class "Default")
      (node (ref "C23") (pin "1") (pinfunction "1_1") (pintype "passive"))
      (node (ref "Q3") (pin "4") (pinfunction "G_4") (pintype "passive"))
      (node (ref "R9") (pin "1") (pinfunction "1_1") (pintype "passive"))
    )
    (net (code "42") (name "Net-(Q4-G)") (class "Default")
      (node (ref "C24") (pin "1") (pinfunction "1_1") (pintype "passive"))
      (node (ref "Q4") (pin "4") (pinfunction "G_4") (pintype "passive"))
      (node (ref "R8") (pin "1") (pinfunction "1_1") (pintype "passive"))
    )
    (net (code "43") (name "Net-(R34-Pad2)") (class "Default")
      (node (ref "R34") (pin "2") (pinfunction "2_2") (pintype "passive"))
      (node (ref "SW1") (pin "1") (pinfunction "1_1") (pintype "passive"))
    )
    (net (code "44") (name "Net-(U1-BST1)") (class "Default")
      (node (ref "R23") (pin "1") (pinfunction "1_1") (pintype "passive"))
      (node (ref "U1") (pin "13") (pinfunction "BST1_13") (pintype "passive"))
    )
    (net (code "45") (name "Net-(U1-BST2)") (class "Default")
      (node (ref "R24") (pin "2") (pinfunction "2_2") (pintype "passive"))
      (node (ref "U1") (pin "18") (pinfunction "BST2_18") (pintype "passive"))
    )
    (net (code "46") (name "Net-(U1-CSN1)") (class "Default")
      (node (ref "C1") (pin "2") (pinfunction "2_2") (pintype "passive"))
      (node (ref "R1") (pin "2") (pinfunction "2_2") (pintype "passive"))
      (node (ref "U1") (pin "10") (pinfunction "CSN1_10") (pintype "passive"))
    )
    (net (code "47") (name "Net-(U1-CSN2)") (class "Default")
      (node (ref "C2") (pin "1") (pinfunction "1_1") (pintype "passive"))
      (node (ref "R3") (pin "2") (pinfunction "2_2") (pintype "passive"))
      (node (ref "U1") (pin "21") (pinfunction "CSN2_21") (pintype "passive"))
    )
    (net (code "48") (name "Net-(U1-PCIN)") (class "Default")
      (node (ref "Q1") (pin "5") (pinfunction "D_5") (pintype "passive"))
      (node (ref "Q1") (pin "6") (pinfunction "D_6") (pintype "passive"))
      (node (ref "Q1") (pin "7") (pinfunction "D_7") (pintype "passive"))
      (node (ref "Q1") (pin "8") (pinfunction "D_8") (pintype "passive"))
      (node (ref "Q1") (pin "9") (pinfunction "D_9") (pintype "passive"))
      (node (ref "R1") (pin "1") (pinfunction "1_1") (pintype "passive"))
      (node (ref "R2") (pin "2") (pinfunction "2_2") (pintype "passive"))
      (node (ref "U1") (pin "11") (pinfunction "PCIN_11") (pintype "passive"))
    )
    (net (code "49") (name "Net-(U1-PCON)") (class "Default")
      (node (ref "Q3") (pin "5") (pinfunction "D_5") (pintype "passive"))
      (node (ref "Q3") (pin "6") (pinfunction "D_6") (pintype "passive"))
      (node (ref "Q3") (pin "7") (pinfunction "D_7") (pintype "passive"))
      (node (ref "Q3") (pin "8") (pinfunction "D_8") (pintype "passive"))
      (node (ref "Q3") (pin "9") (pinfunction "D_9") (pintype "passive"))
      (node (ref "R3") (pin "1") (pinfunction "1_1") (pintype "passive"))
      (node (ref "R4") (pin "1") (pinfunction "1_1") (pintype "passive"))
      (node (ref "U1") (pin "20") (pinfunction "PCON_20") (pintype "passive"))
    )
    (net (code "50") (name "unconnected-(SW1-Pad3)") (class "Default")
      (node (ref "SW1") (pin "3") (pinfunction "3_3") (pintype "passive"))
    )
    (net (code "51") (name "unconnected-(SW1-Pad4)") (class "Default")
      (node (ref "SW1") (pin "4") (pinfunction "4_4") (pintype "passive"))
    )
    (net (code "52") (name "unconnected-(USBC1-SBU1-PadA8)") (class "Default")
      (node (ref "USBC1") (pin "A8") (pinfunction "SBU1_A8") (pintype "passive"))
    )
    (net (code "53") (name "unconnected-(USBC1-SBU2-PadB8)") (class "Default")
      (node (ref "USBC1") (pin "B8") (pinfunction "SBU2_B8") (pintype "passive"))
    )
  )
)
